# C210_0007_Sensors.net
KiCad netlist of a schematic drawn in Altium Designer
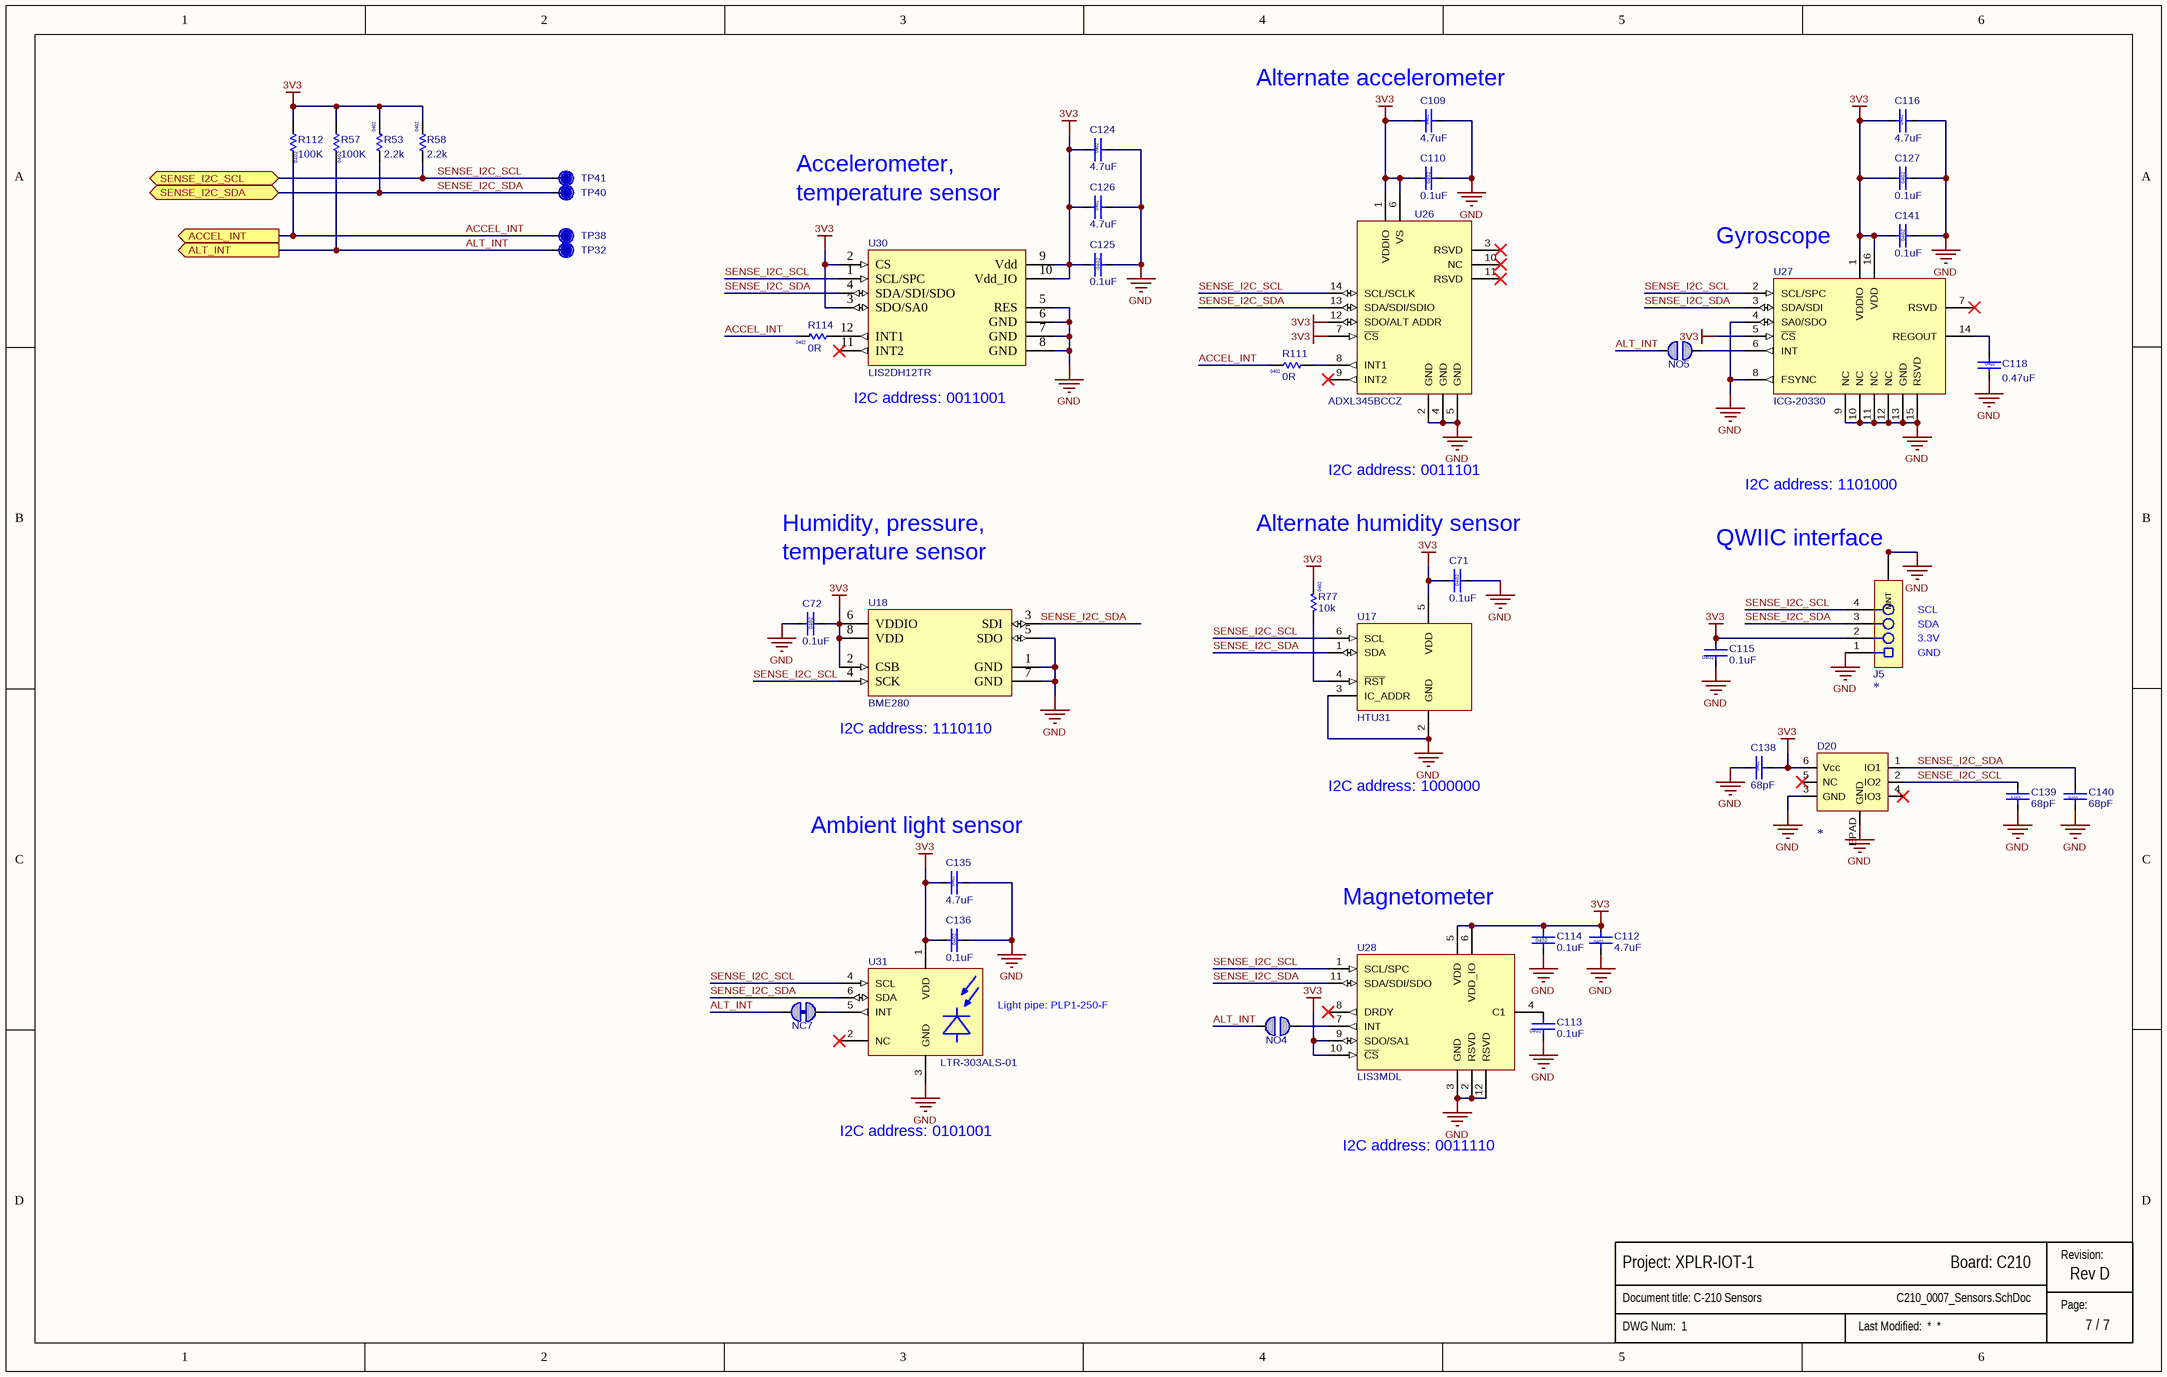
[diagram p0: C210_0007_Sensors.SchDoc]

(export (version "E")
  (design (tool "Eeschema 10.0.6"))
  (components
    (comp (ref "C71")
      (value "0.1uF")
      (footprint "Cap 0402 HD")
      (description "Cap, Ceramic 0.1uF 10V 10% X5R 0402")
      (fields
        (field (name "SIZE") "0402")
        (field (name "PART NUMBER") "120-00016")
        (field (name "MANUFACTURER") "Murata Electronics North America")
      )
      (libsource (lib "Arena_Parts_DB_Lib") (part "Cap Chip"))
    )
    (comp (ref "C72")
      (value "0.1uF")
      (footprint "Cap 0402 HD")
      (description "Cap, Ceramic 0.1uF 10V 10% X5R 0402")
      (fields
        (field (name "SIZE") "0402")
        (field (name "PART NUMBER") "120-00016")
        (field (name "MANUFACTURER") "Murata Electronics North America")
      )
      (libsource (lib "Arena_Parts_DB_Lib") (part "Cap Chip"))
    )
    (comp (ref "C109")
      (value "4.7uF")
      (footprint "Cap 0402 HD")
      (description "Cap, Ceramic 4.7uF 10V 20% X5R 0402")
      (fields
        (field (name "SIZE") "0402")
        (field (name "PART NUMBER") "120-00020")
        (field (name "TOLERANCE") "+/- 20%")
      )
      (libsource (lib "Arena_Parts_DB_Lib") (part "Cap Chip"))
    )
    (comp (ref "C110")
      (value "0.1uF")
      (footprint "Cap 0402 HD")
      (description "Cap, Ceramic 0.1uF 10V 10% X5R 0402")
      (fields
        (field (name "SIZE") "0402")
        (field (name "PART NUMBER") "120-00016")
        (field (name "MANUFACTURER") "Murata Electronics North America")
      )
      (libsource (lib "Arena_Parts_DB_Lib") (part "Cap Chip"))
    )
    (comp (ref "C112")
      (value "4.7uF")
      (footprint "Cap 0402 HD")
      (description "Cap, Ceramic 4.7uF 10V 20% X5R 0402")
      (fields
        (field (name "SIZE") "0402")
        (field (name "PART NUMBER") "120-00020")
        (field (name "TOLERANCE") "+/- 20%")
      )
      (libsource (lib "Arena_Parts_DB_Lib") (part "Cap Chip"))
    )
    (comp (ref "C113")
      (value "0.1uF")
      (footprint "Cap 0402 HD")
      (description "Cap, Ceramic 0.1uF 10V 10% X5R 0402")
      (fields
        (field (name "SIZE") "0402")
        (field (name "PART NUMBER") "120-00016")
        (field (name "MANUFACTURER") "Murata Electronics North America")
      )
      (libsource (lib "Arena_Parts_DB_Lib") (part "Cap Chip"))
    )
    (comp (ref "C114")
      (value "0.1uF")
      (footprint "Cap 0402 HD")
      (description "Cap, Ceramic 0.1uF 10V 10% X5R 0402")
      (fields
        (field (name "SIZE") "0402")
        (field (name "PART NUMBER") "120-00016")
        (field (name "MANUFACTURER") "Murata Electronics North America")
      )
      (libsource (lib "Arena_Parts_DB_Lib") (part "Cap Chip"))
    )
    (comp (ref "C115")
      (value "0.1uF")
      (footprint "Cap 0402 HD")
      (description "Cap, Ceramic 0.1uF 10V 10% X5R 0402")
      (fields
        (field (name "SIZE") "0402")
        (field (name "PART NUMBER") "120-00016")
        (field (name "MANUFACTURER") "Murata Electronics North America")
      )
      (libsource (lib "Arena_Parts_DB_Lib") (part "Cap Chip"))
    )
    (comp (ref "C116")
      (value "4.7uF")
      (footprint "Cap 0402 HD")
      (description "Cap, Ceramic 4.7uF 10V 20% X5R 0402")
      (fields
        (field (name "SIZE") "0402")
        (field (name "PART NUMBER") "120-00020")
        (field (name "TOLERANCE") "+/- 20%")
      )
      (libsource (lib "Arena_Parts_DB_Lib") (part "Cap Chip"))
    )
    (comp (ref "C118")
      (value "0.47uF")
      (footprint "Cap 0402 HD")
      (description "Cap, Ceramic, 0.47UF 10V 10% X5R 0402")
      (fields
        (field (name "SIZE") "0402")
        (field (name "PART NUMBER") "120-00072")
        (field (name "TOLERANCE") "+/- 10%")
      )
      (libsource (lib "Arena_Parts_DB_Lib") (part "Cap Chip"))
    )
    (comp (ref "C124")
      (value "4.7uF")
      (footprint "Cap 0402 HD")
      (description "Cap, Ceramic 4.7uF 10V 20% X5R 0402")
      (fields
        (field (name "SIZE") "0402")
        (field (name "PART NUMBER") "120-00020")
        (field (name "TOLERANCE") "+/- 20%")
      )
      (libsource (lib "Arena_Parts_DB_Lib") (part "Cap Chip"))
    )
    (comp (ref "C125")
      (value "0.1uF")
      (footprint "Cap 0402 HD")
      (description "Cap, Ceramic 0.1uF 10V 10% X5R 0402")
      (fields
        (field (name "SIZE") "0402")
        (field (name "PART NUMBER") "120-00016")
        (field (name "MANUFACTURER") "Murata Electronics North America")
      )
      (libsource (lib "Arena_Parts_DB_Lib") (part "Cap Chip"))
    )
    (comp (ref "C126")
      (value "4.7uF")
      (footprint "Cap 0402 HD")
      (description "Cap, Ceramic 4.7uF 10V 20% X5R 0402")
      (fields
        (field (name "SIZE") "0402")
        (field (name "PART NUMBER") "120-00020")
        (field (name "TOLERANCE") "+/- 20%")
      )
      (libsource (lib "Arena_Parts_DB_Lib") (part "Cap Chip"))
    )
    (comp (ref "C127")
      (value "0.1uF")
      (footprint "Cap 0402 HD")
      (description "Cap, Ceramic 0.1uF 10V 10% X5R 0402")
      (fields
        (field (name "SIZE") "0402")
        (field (name "PART NUMBER") "120-00016")
        (field (name "MANUFACTURER") "Murata Electronics North America")
      )
      (libsource (lib "Arena_Parts_DB_Lib") (part "Cap Chip"))
    )
    (comp (ref "C135")
      (value "4.7uF")
      (footprint "Cap 0402 HD")
      (description "Cap, Ceramic 4.7uF 10V 20% X5R 0402")
      (fields
        (field (name "SIZE") "0402")
        (field (name "PART NUMBER") "120-00020")
        (field (name "TOLERANCE") "+/- 20%")
      )
      (libsource (lib "Arena_Parts_DB_Lib") (part "Cap Chip"))
    )
    (comp (ref "C136")
      (value "0.1uF")
      (footprint "Cap 0402 HD")
      (description "Cap, Ceramic 0.1uF 10V 10% X5R 0402")
      (fields
        (field (name "SIZE") "0402")
        (field (name "PART NUMBER") "120-00016")
        (field (name "MANUFACTURER") "Murata Electronics North America")
      )
      (libsource (lib "Arena_Parts_DB_Lib") (part "Cap Chip"))
    )
    (comp (ref "C138")
      (value "68pF")
      (footprint "Cap 0402 HD")
      (description "Cap, Ceramic, 68pF, 50V, 1%, NP0, 0402")
      (fields
        (field (name "SIZE") "0402")
        (field (name "PART NUMBER") "120-00047")
        (field (name "TOLERANCE") "+/- 1%")
      )
      (libsource (lib "Arena_Parts_DB_Lib") (part "Cap Chip"))
    )
    (comp (ref "C139")
      (value "68pF")
      (footprint "Cap 0402 HD")
      (description "Cap, Ceramic, 68pF, 50V, 1%, NP0, 0402")
      (fields
        (field (name "SIZE") "0402")
        (field (name "PART NUMBER") "120-00047")
        (field (name "TOLERANCE") "+/- 1%")
      )
      (libsource (lib "Arena_Parts_DB_Lib") (part "Cap Chip"))
    )
    (comp (ref "C140")
      (value "68pF")
      (footprint "Cap 0402 HD")
      (description "Cap, Ceramic, 68pF, 50V, 1%, NP0, 0402")
      (fields
        (field (name "SIZE") "0402")
        (field (name "PART NUMBER") "120-00047")
        (field (name "TOLERANCE") "+/- 1%")
      )
      (libsource (lib "Arena_Parts_DB_Lib") (part "Cap Chip"))
    )
    (comp (ref "C141")
      (value "0.1uF")
      (footprint "Cap 0402 HD")
      (description "Cap, Ceramic 0.1uF 10V 10% X5R 0402")
      (fields
        (field (name "SIZE") "0402")
        (field (name "PART NUMBER") "120-00016")
        (field (name "MANUFACTURER") "Murata Electronics North America")
      )
      (libsource (lib "Arena_Parts_DB_Lib") (part "Cap Chip"))
    )
    (comp (ref "D20")
      (value "~")
      (footprint "TPD3E001DRSR")
      (description "TVS Diode, ESD High Speed 3-Channel Array, WSON-6, 3mmX3mm")
      (fields (field (name "VOLTAGE") "5.5V") (field (name "MANUFACTURER P/N") "*"))
      (libsource (lib "TPD3E001DRSR") (part "TPD3E001"))
    )
    (comp (ref "J5")
      (value "SM04B-SRSS-TB(LF)(SN)")
      (footprint "SM04B-SRSS-TB(LF)(SN)")
      (description "Conn, Header, SMD, 1mm Pitch, 4 Pin, R/A, White")
      (fields (field (name "VOLTAGE") "None") (field (name "MANUFACTURER P/N") "*"))
      (libsource (lib "SM04B-SRSS") (part "SM04B-SRSS-TB(LF)(SN)"))
    )
    (comp (ref "NC7")
      (value "Solderbridge-ShortDNP")
      (footprint "Solderbridge-Short")
      (description "Solderbridge-Short")
      (fields (field (name "ADDED BY") "Paul B"))
      (libsource (lib "PCB_Misc") (part "Solderbridge-Short"))
    )
    (comp (ref "NO4")
      (value "Solderbridge-OpenDNP")
      (footprint "Solderbridge-Open")
      (description "Solderbridge-Open")
      (fields (field (name "ADDED BY") "Paul B"))
      (libsource (lib "PCB_Misc") (part "Solderbridge-Open"))
    )
    (comp (ref "NO5")
      (value "Solderbridge-OpenDNP")
      (footprint "Solderbridge-Open")
      (description "Solderbridge-Open")
      (fields (field (name "ADDED BY") "Paul B"))
      (libsource (lib "PCB_Misc") (part "Solderbridge-Open"))
    )
    (comp (ref "R53")
      (value "2.2k")
      (footprint "RES 0402 HD")
      (description "Resistor, 2.2Kohm, 1%, 1/16W, 0402")
      (fields
        (field (name "SIZE") "0402")
        (field (name "PART NUMBER") "180-00023")
        (field (name "POWER") "1/16W")
      )
      (libsource (lib "Arena_Parts_DB_Lib") (part "Res sm"))
    )
    (comp (ref "R57")
      (value "100K")
      (footprint "RES 0402 HD")
      (description "Resistor 100K ohm 1% 1/16W, 0402")
      (fields
        (field (name "SIZE") "0402")
        (field (name "PART NUMBER") "180-00093")
        (field (name "POWER") "1/16W")
      )
      (libsource (lib "Arena_Parts_DB_Lib") (part "Res sm"))
    )
    (comp (ref "R58")
      (value "2.2k")
      (footprint "RES 0402 HD")
      (description "Resistor, 2.2Kohm, 1%, 1/16W, 0402")
      (fields
        (field (name "SIZE") "0402")
        (field (name "PART NUMBER") "180-00023")
        (field (name "POWER") "1/16W")
      )
      (libsource (lib "Arena_Parts_DB_Lib") (part "Res sm"))
    )
    (comp (ref "R77")
      (value "10k")
      (footprint "RES 0402 HD")
      (description "Resistor 10k ohm 1% 1/16W, 0402")
      (fields
        (field (name "SIZE") "0402")
        (field (name "PART NUMBER") "180-00024")
        (field (name "POWER") "1/16W")
      )
      (libsource (lib "Arena_Parts_DB_Lib") (part "Res sm"))
    )
    (comp (ref "R111")
      (value "0R")
      (footprint "RES 0402 HD")
      (description "Resistor 0 ohm 1/16W 0402")
      (fields
        (field (name "SIZE") "0402")
        (field (name "PART NUMBER") "180-00020")
        (field (name "POWER") "1/16W")
      )
      (libsource (lib "Arena_Parts_DB_Lib") (part "Res sm"))
    )
    (comp (ref "R112")
      (value "100K")
      (footprint "RES 0402 HD")
      (description "Resistor 100K ohm 1% 1/16W, 0402")
      (fields
        (field (name "SIZE") "0402")
        (field (name "PART NUMBER") "180-00093")
        (field (name "POWER") "1/16W")
      )
      (libsource (lib "Arena_Parts_DB_Lib") (part "Res sm"))
    )
    (comp (ref "R114")
      (value "0R")
      (footprint "RES 0402 HD")
      (description "Resistor 0 ohm 1/16W 0402")
      (fields
        (field (name "SIZE") "0402")
        (field (name "PART NUMBER") "180-00020")
        (field (name "POWER") "1/16W")
      )
      (libsource (lib "Arena_Parts_DB_Lib") (part "Res sm"))
    )
    (comp (ref "TP32")
      (value "TP")
      (footprint "TP12R")
      (description "Testpoint, Round 1.0mm Dia")
      (fields
        (field (name "PART NUMBER") "TP10R")
        (field (name "ADDED BY") "Jeremy D")
        (field (name "CHECKED BY") "Paul B")
      )
      (libsource (lib "PCB_Misc") (part "TP_R"))
    )
    (comp (ref "TP38")
      (value "TP")
      (footprint "TP12R")
      (description "Testpoint, Round 1.0mm Dia")
      (fields
        (field (name "PART NUMBER") "TP10R")
        (field (name "ADDED BY") "Jeremy D")
        (field (name "CHECKED BY") "Paul B")
      )
      (libsource (lib "PCB_Misc") (part "TP_R"))
    )
    (comp (ref "TP40")
      (value "TP")
      (footprint "TP12R")
      (description "Testpoint, Round 1.0mm Dia")
      (fields
        (field (name "PART NUMBER") "TP10R")
        (field (name "ADDED BY") "Jeremy D")
        (field (name "CHECKED BY") "Paul B")
      )
      (libsource (lib "PCB_Misc") (part "TP_R"))
    )
    (comp (ref "TP41")
      (value "TP")
      (footprint "TP12R")
      (description "Testpoint, Round 1.0mm Dia")
      (fields
        (field (name "PART NUMBER") "TP10R")
        (field (name "ADDED BY") "Jeremy D")
        (field (name "CHECKED BY") "Paul B")
      )
      (libsource (lib "PCB_Misc") (part "TP_R"))
    )
    (comp (ref "U17")
      (value "HTU31")
      (footprint "HTU31")
      (description "SENSOR, Humidity, I2C, SMT, DFN-6 2.5mmX2.5mm")
      (fields (field (name "MANUFACTURER PART NUMBER 1") "HTU31"))
      (libsource (lib "HTU31") (part "HTU31"))
    )
    (comp (ref "U18")
      (value "250-00039")
      (footprint "DFN0.65P-8Pin")
      (description "SENSOR PRESSURE HUMIDITY TEMP")
      (fields
        (field (name "MANUFACTURER P/N") "BME280")
        (field (name "MANUFACTURER") "Bosch Sensortec")
        (field (name "VOLTAGE") "3.6V")
      )
      (libsource (lib "Arena_Lib") (part "BME280"))
    )
    (comp (ref "U26")
      (value "ADXL345BCCZ")
      (footprint "ADXL345")
      (description "SENSOR, ACCELEROMETER, 3-AXIS, I2C, SMT, +/-16g, LGA-14 3mmX5mm")
      (fields (field (name "MANUFACTURER PART NUMBER 1") "ADXL345BCCZ"))
      (libsource (lib "ADXL345") (part "ADXL345"))
    )
    (comp (ref "U27")
      (value "ICG-20330")
      (footprint "ICG-20330")
      (description "SENSOR, Gyroscope, I2C, 3-AXIS, 1.7-3.45V, SMT, LGA-16, 3mmX3mm")
      (fields (field (name "MANUFACTURER PART NUMBER 1") "ICG-20330") (field (name "VOLTAGE") "1.9-3.6V"))
      (libsource (lib "ICG-20330") (part "ICG-20330"))
    )
    (comp (ref "U28")
      (value "LIS3MDL")
      (footprint "LIS3MDL")
      (description "SENSOR, MAGNETOMETER, I2C, 3-AXIS, 1.9-3.6V, SMT, LGA-12, 2mmX2mm")
      (fields (field (name "MANUFACTURER PART NUMBER 1") "LIS3MDL") (field (name "VOLTAGE") "1.9-3.6V"))
      (libsource (lib "LIS3MDL") (part "LIS3MDL"))
    )
    (comp (ref "U30")
      (value "250-00008")
      (footprint "LGA0.5P_4x4_12Pin")
      (description "Accelerometer, 2G-16G Max, 12bit, LGA-12")
      (fields
        (field (name "MANUFACTURER P/N") "LIS2DH12TR")
        (field (name "MANUFACTURER") "STMicroelectronics")
        (field (name "VOLTAGE") "3.6V")
      )
      (libsource (lib "Arena_Lib") (part "LIS2DH12"))
    )
    (comp (ref "U31")
      (value "LTR-303ALS-01")
      (footprint "LTR-303ALS-01")
      (description "SENSOR, AMBIENT LIGHT, I2C, SMT, GNSS, DFN-6 2mmX2mm")
      (fields (field (name "MANUFACTURER PART NUMBER 1") "LTR-303ALS-01"))
      (libsource (lib "LTR-303ALS-01") (part "LTR-303ALS-01"))
    )
  )
  (nets
    (net (code "1") (name "/ACCEL_INT") (class "Default")
      (node (ref "R111") (pin "2") (pinfunction "2_2") (pintype "passive"))
      (node (ref "R112") (pin "2") (pinfunction "2_2") (pintype "passive"))
      (node (ref "R114") (pin "2") (pinfunction "2_2") (pintype "passive"))
      (node (ref "TP38") (pin "1") (pintype "passive"))
    )
    (net (code "2") (name "/ALT_INT") (class "Default")
      (node (ref "NC7") (pin "2") (pinfunction "2_2") (pintype "passive"))
      (node (ref "NO4") (pin "2") (pinfunction "2_2") (pintype "passive"))
      (node (ref "NO5") (pin "2") (pinfunction "2_2") (pintype "passive"))
      (node (ref "R57") (pin "2") (pinfunction "2_2") (pintype "passive"))
      (node (ref "TP32") (pin "1") (pintype "passive"))
    )
    (net (code "3") (name "/SENSE_I2C_SCL") (class "Default")
      (node (ref "C139") (pin "2") (pinfunction "2_2") (pintype "passive"))
      (node (ref "D20") (pin "2") (pinfunction "IO2_2") (pintype "passive"))
      (node (ref "J5") (pin "4") (pinfunction "4_4") (pintype "passive"))
      (node (ref "R58") (pin "1") (pinfunction "1_1") (pintype "passive"))
      (node (ref "TP41") (pin "1") (pintype "passive"))
      (node (ref "U17") (pin "6") (pinfunction "SCL_6") (pintype "input"))
      (node (ref "U18") (pin "4") (pinfunction "SCK_4") (pintype "input"))
      (node (ref "U26") (pin "14") (pinfunction "SCL/SCLK_14") (pintype "bidirectional"))
      (node (ref "U27") (pin "2") (pinfunction "SCL/SPC_2") (pintype "input"))
      (node (ref "U28") (pin "1") (pinfunction "SCL/SPC_1") (pintype "input"))
      (node (ref "U30") (pin "1") (pinfunction "SCL/SPC_1") (pintype "input"))
      (node (ref "U31") (pin "4") (pinfunction "SCL_4") (pintype "input"))
    )
    (net (code "4") (name "/SENSE_I2C_SDA") (class "Default")
      (node (ref "C140") (pin "2") (pinfunction "2_2") (pintype "passive"))
      (node (ref "D20") (pin "1") (pinfunction "IO1_1") (pintype "passive"))
      (node (ref "J5") (pin "3") (pinfunction "3_3") (pintype "passive"))
      (node (ref "R53") (pin "1") (pinfunction "1_1") (pintype "passive"))
      (node (ref "TP40") (pin "1") (pintype "passive"))
      (node (ref "U17") (pin "1") (pinfunction "SDA_1") (pintype "bidirectional"))
      (node (ref "U18") (pin "3") (pinfunction "SDI_3") (pintype "bidirectional"))
      (node (ref "U26") (pin "13") (pinfunction "SDA/SDI/SDIO_13") (pintype "bidirectional"))
      (node (ref "U27") (pin "3") (pinfunction "SDA/SDI_3") (pintype "bidirectional"))
      (node (ref "U28") (pin "11") (pinfunction "SDA/SDI/SDO_11") (pintype "bidirectional"))
      (node (ref "U30") (pin "4") (pinfunction "SDA/SDI/SDO_4") (pintype "bidirectional"))
      (node (ref "U31") (pin "6") (pinfunction "SDA_6") (pintype "bidirectional"))
    )
    (net (code "5") (name "3V3") (class "Default")
      (node (ref "C109") (pin "1") (pinfunction "1_1") (pintype "passive"))
      (node (ref "C110") (pin "1") (pinfunction "1_1") (pintype "passive"))
      (node (ref "C112") (pin "2") (pinfunction "2_2") (pintype "passive"))
      (node (ref "C114") (pin "2") (pinfunction "2_2") (pintype "passive"))
      (node (ref "C115") (pin "2") (pinfunction "2_2") (pintype "passive"))
      (node (ref "C116") (pin "1") (pinfunction "1_1") (pintype "passive"))
      (node (ref "C124") (pin "1") (pinfunction "1_1") (pintype "passive"))
      (node (ref "C125") (pin "1") (pinfunction "1_1") (pintype "passive"))
      (node (ref "C126") (pin "1") (pinfunction "1_1") (pintype "passive"))
      (node (ref "C127") (pin "1") (pinfunction "1_1") (pintype "passive"))
      (node (ref "C135") (pin "1") (pinfunction "1_1") (pintype "passive"))
      (node (ref "C136") (pin "1") (pinfunction "1_1") (pintype "passive"))
      (node (ref "C138") (pin "2") (pinfunction "2_2") (pintype "passive"))
      (node (ref "C141") (pin "1") (pinfunction "1_1") (pintype "passive"))
      (node (ref "C71") (pin "1") (pinfunction "1_1") (pintype "passive"))
      (node (ref "C72") (pin "2") (pinfunction "2_2") (pintype "passive"))
      (node (ref "D20") (pin "6") (pinfunction "Vcc_6") (pintype "power_in"))
      (node (ref "J5") (pin "2") (pinfunction "2_2") (pintype "passive"))
      (node (ref "R112") (pin "1") (pinfunction "1_1") (pintype "passive"))
      (node (ref "R53") (pin "2") (pinfunction "2_2") (pintype "passive"))
      (node (ref "R57") (pin "1") (pinfunction "1_1") (pintype "passive"))
      (node (ref "R58") (pin "2") (pinfunction "2_2") (pintype "passive"))
      (node (ref "R77") (pin "2") (pinfunction "2_2") (pintype "passive"))
      (node (ref "U17") (pin "5") (pinfunction "VDD_5") (pintype "power_in"))
      (node (ref "U18") (pin "2") (pinfunction "CSB_2") (pintype "input"))
      (node (ref "U18") (pin "6") (pinfunction "VDDIO_6") (pintype "power_in"))
      (node (ref "U18") (pin "8") (pinfunction "VDD_8") (pintype "power_in"))
      (node (ref "U26") (pin "1") (pinfunction "VDDIO_1") (pintype "power_in"))
      (node (ref "U26") (pin "12") (pinfunction "SDO/ALT_ADDR_12") (pintype "bidirectional"))
      (node (ref "U26") (pin "6") (pinfunction "VS_6") (pintype "power_in"))
      (node (ref "U26") (pin "7") (pinfunction "~{CS}_7") (pintype "input"))
      (node (ref "U27") (pin "1") (pinfunction "VDDIO_1") (pintype "power_in"))
      (node (ref "U27") (pin "16") (pinfunction "VDD_16") (pintype "power_in"))
      (node (ref "U27") (pin "5") (pinfunction "~{CS}_5") (pintype "input"))
      (node (ref "U28") (pin "10") (pinfunction "~{CS}_10") (pintype "input"))
      (node (ref "U28") (pin "5") (pinfunction "VDD_5") (pintype "power_in"))
      (node (ref "U28") (pin "6") (pinfunction "VDD_IO_6") (pintype "power_in"))
      (node (ref "U28") (pin "9") (pinfunction "SDO/SA1_9") (pintype "bidirectional"))
      (node (ref "U30") (pin "10") (pinfunction "Vdd_IO_10") (pintype "power_in"))
      (node (ref "U30") (pin "2") (pinfunction "CS_2") (pintype "input"))
      (node (ref "U30") (pin "3") (pinfunction "SDO/SA0_3") (pintype "bidirectional"))
      (node (ref "U30") (pin "9") (pinfunction "Vdd_9") (pintype "power_in"))
      (node (ref "U31") (pin "1") (pinfunction "VDD_1") (pintype "power_in"))
    )
    (net (code "6") (name "GND") (class "Default")
      (node (ref "C109") (pin "2") (pinfunction "2_2") (pintype "passive"))
      (node (ref "C110") (pin "2") (pinfunction "2_2") (pintype "passive"))
      (node (ref "C112") (pin "1") (pinfunction "1_1") (pintype "passive"))
      (node (ref "C113") (pin "1") (pinfunction "1_1") (pintype "passive"))
      (node (ref "C114") (pin "1") (pinfunction "1_1") (pintype "passive"))
      (node (ref "C115") (pin "1") (pinfunction "1_1") (pintype "passive"))
      (node (ref "C116") (pin "2") (pinfunction "2_2") (pintype "passive"))
      (node (ref "C118") (pin "2") (pinfunction "2_2") (pintype "passive"))
      (node (ref "C124") (pin "2") (pinfunction "2_2") (pintype "passive"))
      (node (ref "C125") (pin "2") (pinfunction "2_2") (pintype "passive"))
      (node (ref "C126") (pin "2") (pinfunction "2_2") (pintype "passive"))
      (node (ref "C127") (pin "2") (pinfunction "2_2") (pintype "passive"))
      (node (ref "C135") (pin "2") (pinfunction "2_2") (pintype "passive"))
      (node (ref "C136") (pin "2") (pinfunction "2_2") (pintype "passive"))
      (node (ref "C138") (pin "1") (pinfunction "1_1") (pintype "passive"))
      (node (ref "C139") (pin "1") (pinfunction "1_1") (pintype "passive"))
      (node (ref "C140") (pin "1") (pinfunction "1_1") (pintype "passive"))
      (node (ref "C141") (pin "2") (pinfunction "2_2") (pintype "passive"))
      (node (ref "C71") (pin "2") (pinfunction "2_2") (pintype "passive"))
      (node (ref "C72") (pin "1") (pinfunction "1_1") (pintype "passive"))
      (node (ref "D20") (pin "3") (pinfunction "GND_3") (pintype "power_in"))
      (node (ref "D20") (pin "EPAD") (pinfunction "GND_EPAD") (pintype "power_in"))
      (node (ref "J5") (pin "1") (pinfunction "1_1") (pintype "passive"))
      (node (ref "J5") (pin "M1") (pinfunction "MNT_M1") (pintype "passive"))
      (node (ref "J5") (pin "M2") (pinfunction "MNT_M2") (pintype "passive"))
      (node (ref "U17") (pin "2") (pinfunction "GND_2") (pintype "power_in"))
      (node (ref "U17") (pin "3") (pinfunction "IC_ADDR_3") (pintype "passive"))
      (node (ref "U18") (pin "1") (pinfunction "GND_1") (pintype "power_in"))
      (node (ref "U18") (pin "5") (pinfunction "SDO_5") (pintype "bidirectional"))
      (node (ref "U18") (pin "7") (pinfunction "GND_7") (pintype "power_in"))
      (node (ref "U26") (pin "2") (pinfunction "GND_2") (pintype "power_in"))
      (node (ref "U26") (pin "4") (pinfunction "GND_4") (pintype "power_in"))
      (node (ref "U26") (pin "5") (pinfunction "GND_5") (pintype "power_in"))
      (node (ref "U27") (pin "10") (pinfunction "NC_10") (pintype "passive"))
      (node (ref "U27") (pin "11") (pinfunction "NC_11") (pintype "passive"))
      (node (ref "U27") (pin "12") (pinfunction "NC_12") (pintype "passive"))
      (node (ref "U27") (pin "13") (pinfunction "GND_13") (pintype "power_in"))
      (node (ref "U27") (pin "15") (pinfunction "RSVD_15") (pintype "passive"))
      (node (ref "U27") (pin "4") (pinfunction "SA0/SDO_4") (pintype "bidirectional"))
      (node (ref "U27") (pin "8") (pinfunction "FSYNC_8") (pintype "output"))
      (node (ref "U27") (pin "9") (pinfunction "NC_9") (pintype "passive"))
      (node (ref "U28") (pin "12") (pinfunction "RSVD_12") (pintype "passive"))
      (node (ref "U28") (pin "2") (pinfunction "RSVD_2") (pintype "passive"))
      (node (ref "U28") (pin "3") (pinfunction "GND_3") (pintype "power_in"))
      (node (ref "U30") (pin "5") (pinfunction "RES_5") (pintype "passive"))
      (node (ref "U30") (pin "6") (pinfunction "GND_6") (pintype "power_in"))
      (node (ref "U30") (pin "7") (pinfunction "GND_7") (pintype "power_in"))
      (node (ref "U30") (pin "8") (pinfunction "GND_8") (pintype "power_in"))
      (node (ref "U31") (pin "3") (pinfunction "GND_3") (pintype "power_in"))
    )
    (net (code "7") (name "Net-(U17-~{RST})") (class "Default")
      (node (ref "R77") (pin "1") (pinfunction "1_1") (pintype "passive"))
      (node (ref "U17") (pin "4") (pinfunction "~{RST}_4") (pintype "input"))
    )
    (net (code "8") (name "Net-(U26-INT1)") (class "Default")
      (node (ref "R111") (pin "1") (pinfunction "1_1") (pintype "passive"))
      (node (ref "U26") (pin "8") (pinfunction "INT1_8") (pintype "output"))
    )
    (net (code "9") (name "Net-(U27-INT)") (class "Default")
      (node (ref "NO5") (pin "1") (pinfunction "1_1") (pintype "passive"))
      (node (ref "U27") (pin "6") (pinfunction "INT_6") (pintype "output"))
    )
    (net (code "10") (name "Net-(U27-REGOUT)") (class "Default")
      (node (ref "C118") (pin "1") (pinfunction "1_1") (pintype "passive"))
      (node (ref "U27") (pin "14") (pinfunction "REGOUT_14") (pintype "passive"))
    )
    (net (code "11") (name "Net-(U28-C1)") (class "Default")
      (node (ref "C113") (pin "2") (pinfunction "2_2") (pintype "passive"))
      (node (ref "U28") (pin "4") (pinfunction "C1_4") (pintype "passive"))
    )
    (net (code "12") (name "Net-(U28-INT)") (class "Default")
      (node (ref "NO4") (pin "1") (pinfunction "1_1") (pintype "passive"))
      (node (ref "U28") (pin "7") (pinfunction "INT_7") (pintype "output"))
    )
    (net (code "13") (name "Net-(U30-INT1)") (class "Default")
      (node (ref "R114") (pin "1") (pinfunction "1_1") (pintype "passive"))
      (node (ref "U30") (pin "12") (pinfunction "INT1_12") (pintype "output"))
    )
    (net (code "14") (name "Net-(U31-INT)") (class "Default")
      (node (ref "NC7") (pin "1") (pinfunction "1_1") (pintype "passive"))
      (node (ref "U31") (pin "5") (pinfunction "INT_5") (pintype "output"))
    )
    (net (code "15") (name "unconnected-(D20-IO3-Pad4)") (class "Default")
      (node (ref "D20") (pin "4") (pinfunction "IO3_4") (pintype "passive+no_connect"))
    )
    (net (code "16") (name "unconnected-(D20-NC-Pad5)") (class "Default")
      (node (ref "D20") (pin "5") (pinfunction "NC_5") (pintype "passive+no_connect"))
    )
    (net (code "17") (name "unconnected-(U26-INT2-Pad9)") (class "Default")
      (node (ref "U26") (pin "9") (pinfunction "INT2_9") (pintype "output+no_connect"))
    )
    (net (code "18") (name "unconnected-(U26-NC-Pad10)") (class "Default")
      (node (ref "U26") (pin "10") (pinfunction "NC_10") (pintype "passive+no_connect"))
    )
    (net (code "19") (name "unconnected-(U26-RSVD-Pad3)") (class "Default")
      (node (ref "U26") (pin "3") (pinfunction "RSVD_3") (pintype "passive+no_connect"))
    )
    (net (code "20") (name "unconnected-(U26-RSVD-Pad11)") (class "Default")
      (node (ref "U26") (pin "11") (pinfunction "RSVD_11") (pintype "passive+no_connect"))
    )
    (net (code "21") (name "unconnected-(U27-RSVD-Pad7)") (class "Default")
      (node (ref "U27") (pin "7") (pinfunction "RSVD_7") (pintype "passive+no_connect"))
    )
    (net (code "22") (name "unconnected-(U28-DRDY-Pad8)") (class "Default")
      (node (ref "U28") (pin "8") (pinfunction "DRDY_8") (pintype "output+no_connect"))
    )
    (net (code "23") (name "unconnected-(U30-INT2-Pad11)") (class "Default")
      (node (ref "U30") (pin "11") (pinfunction "INT2_11") (pintype "output+no_connect"))
    )
    (net (code "24") (name "unconnected-(U31-NC-Pad2)") (class "Default")
      (node (ref "U31") (pin "2") (pinfunction "NC_2") (pintype "passive+no_connect"))
    )
  )
)
